# current_sensor.net
KiCad netlist of a schematic drawn in EAGLE
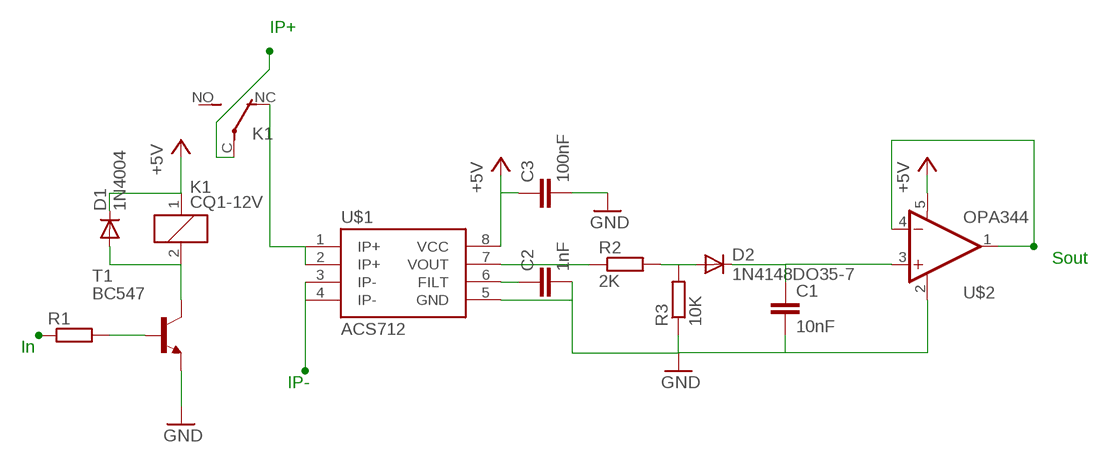
[diagram p0: schematic, sheet 1]

(export (version "E")
  (design (tool "Eeschema 10.0.6"))
  (components
    (comp (ref "C1")
      (value "10nF")
      (footprint "eagle-import:C5B2.5")
      (libsource (lib "eagle-import") (part "C5/2.5"))
    )
    (comp (ref "C2")
      (value "1nF")
      (footprint "eagle-import:C7.5B3")
      (libsource (lib "eagle-import") (part "C7.5/3"))
    )
    (comp (ref "C3")
      (value "100nF")
      (footprint "eagle-import:C7.5B3")
      (libsource (lib "eagle-import") (part "C7.5/3"))
    )
    (comp (ref "D1")
      (value "1N4004")
      (footprint "eagle-import:DO41-10")
      (libsource (lib "eagle-import") (part "1N4004"))
    )
    (comp (ref "D2")
      (value "1N4148DO35-7")
      (footprint "eagle-import:DO35-7")
      (libsource (lib "eagle-import") (part "1N4148DO35-7"))
    )
    (comp (ref "K1")
      (value "CQ1-12V")
      (footprint "eagle-import:CQ1")
      (libsource (lib "eagle-import") (part "CQ1-12V"))
    )
    (comp (ref "R1")
      (value "R-EU_0207/12")
      (footprint "eagle-import:0207_12")
      (libsource (lib "eagle-import") (part "R-EU_0207/12"))
    )
    (comp (ref "R2")
      (value "2K")
      (footprint "eagle-import:0207_12")
      (libsource (lib "eagle-import") (part "R-EU_0207/12"))
    )
    (comp (ref "R3")
      (value "10K")
      (footprint "eagle-import:0207_12")
      (libsource (lib "eagle-import") (part "R-EU_0207/12"))
    )
    (comp (ref "T1")
      (value "BC547")
      (footprint "eagle-import:TO92")
      (libsource (lib "eagle-import") (part "BC547"))
    )
    (comp (ref "U$1")
      (value "ACS712")
      (footprint "eagle-import:SO08")
      (libsource (lib "eagle-import") (part "ACS712"))
    )
    (comp (ref "U$2")
      (value "OPA344")
      (footprint "eagle-import:SOT23-5")
      (libsource (lib "eagle-import") (part "OPA344"))
    )
  )
  (nets
    (net (code "1") (name "+5V") (class "Default")
      (node (ref "C3") (pin "1") (pinfunction "1_1") (pintype "passive"))
      (node (ref "D1") (pin "C") (pinfunction "C_C") (pintype "passive"))
      (node (ref "K1") (pin "1") (pinfunction "1_1") (pintype "passive"))
      (node (ref "U$1") (pin "8") (pinfunction "VCC_8") (pintype "bidirectional"))
      (node (ref "U$2") (pin "5") (pinfunction "V+_5") (pintype "power_in"))
    )
    (net (code "2") (name "GND") (class "Default")
      (node (ref "C1") (pin "2") (pinfunction "2_2") (pintype "passive"))
      (node (ref "C2") (pin "2") (pinfunction "2_2") (pintype "passive"))
      (node (ref "C3") (pin "2") (pinfunction "2_2") (pintype "passive"))
      (node (ref "R3") (pin "1") (pinfunction "1_1") (pintype "passive"))
      (node (ref "T1") (pin "1") (pinfunction "E_1") (pintype "passive"))
      (node (ref "U$1") (pin "5") (pinfunction "GND_5") (pintype "bidirectional"))
      (node (ref "U$2") (pin "2") (pinfunction "V-_2") (pintype "power_in"))
    )
    (net (code "3") (name "Net-(D2-PadA)") (class "Default")
      (node (ref "D2") (pin "A") (pinfunction "A_A") (pintype "passive"))
      (node (ref "R2") (pin "2") (pinfunction "2_2") (pintype "passive"))
      (node (ref "R3") (pin "2") (pinfunction "2_2") (pintype "passive"))
    )
    (net (code "4") (name "Net-(K1B-O)") (class "Default")
      (node (ref "K1") (pin "NC") (pinfunction "O_NC") (pintype "passive"))
      (node (ref "U$1") (pin "1") (pinfunction "IP+_1") (pintype "bidirectional"))
      (node (ref "U$1") (pin "2") (pinfunction "IP+_2") (pintype "bidirectional"))
    )
    (net (code "5") (name "Net-(T1-B)") (class "Default")
      (node (ref "R1") (pin "2") (pinfunction "2_2") (pintype "passive"))
      (node (ref "T1") (pin "2") (pinfunction "B_2") (pintype "passive"))
    )
    (net (code "6") (name "Net-(T1-C)") (class "Default")
      (node (ref "D1") (pin "A") (pinfunction "A_A") (pintype "passive"))
      (node (ref "K1") (pin "2") (pinfunction "2_2") (pintype "passive"))
      (node (ref "T1") (pin "3") (pinfunction "C_3") (pintype "passive"))
    )
    (net (code "7") (name "Net-(U$1-FILT)") (class "Default")
      (node (ref "C2") (pin "1") (pinfunction "1_1") (pintype "passive"))
      (node (ref "U$1") (pin "6") (pinfunction "FILT_6") (pintype "bidirectional"))
    )
    (net (code "8") (name "Net-(U$1-IP--Pad3)") (class "Default")
      (node (ref "U$1") (pin "3") (pinfunction "IP-_3") (pintype "bidirectional"))
      (node (ref "U$1") (pin "4") (pinfunction "IP-_4") (pintype "bidirectional"))
    )
    (net (code "9") (name "Net-(U$1-VOUT)") (class "Default")
      (node (ref "R2") (pin "1") (pinfunction "1_1") (pintype "passive"))
      (node (ref "U$1") (pin "7") (pinfunction "VOUT_7") (pintype "bidirectional"))
    )
    (net (code "10") (name "Net-(U$2-+IN)") (class "Default")
      (node (ref "C1") (pin "1") (pinfunction "1_1") (pintype "passive"))
      (node (ref "D2") (pin "C") (pinfunction "C_C") (pintype "passive"))
      (node (ref "U$2") (pin "3") (pinfunction "+IN_3") (pintype "input"))
    )
    (net (code "11") (name "Net-(U$2--IN)") (class "Default")
      (node (ref "U$2") (pin "1") (pinfunction "OUT_1") (pintype "output"))
      (node (ref "U$2") (pin "4") (pinfunction "-IN_4") (pintype "input"))
    )
    (net (code "12") (name "unconnected-(K1B-P-PadC)") (class "Default")
      (node (ref "K1") (pin "C") (pinfunction "P_C") (pintype "passive"))
    )
    (net (code "13") (name "unconnected-(K1B-S-PadNO)") (class "Default")
      (node (ref "K1") (pin "NO") (pinfunction "S_NO") (pintype "passive"))
    )
    (net (code "14") (name "unconnected-(R1-Pad1)") (class "Default")
      (node (ref "R1") (pin "1") (pinfunction "1_1") (pintype "passive"))
    )
  )
)
